# SoftPoweroff.net
KiCad netlist of a schematic drawn in EAGLE
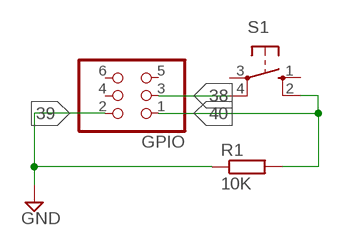
[diagram p0: schematic, sheet 1]

(export (version "E")
  (design (tool "Eeschema 10.0.6"))
  (components
    (comp (ref "GPIO")
      (value "PINHD-2X3")
      (footprint "eagle-import:2X03")
      (libsource (lib "eagle-import") (part "PINHD-2X3"))
    )
    (comp (ref "R1")
      (value "10K")
      (footprint "eagle-import:0207_10")
      (libsource (lib "eagle-import") (part "R-EU_0207/10"))
    )
    (comp (ref "S1")
      (value "10-XX")
      (footprint "eagle-import:B3F-10XX")
      (fields (field (name "MPN") "B3F-1000"))
      (libsource (lib "eagle-import") (part "10-XX"))
    )
  )
  (nets
    (net (code "1") (name "38") (class "Default")
      (node (ref "GPIO") (pin "3") (pinfunction "3_3") (pintype "passive"))
      (node (ref "S1") (pin "4") (pinfunction "P1_4") (pintype "passive"))
    )
    (net (code "2") (name "39") (class "Default")
      (node (ref "GPIO") (pin "2") (pinfunction "2_2") (pintype "passive"))
      (node (ref "R1") (pin "1") (pinfunction "1_1") (pintype "passive"))
    )
    (net (code "3") (name "40") (class "Default")
      (node (ref "GPIO") (pin "1") (pinfunction "1_1") (pintype "passive"))
      (node (ref "R1") (pin "2") (pinfunction "2_2") (pintype "passive"))
      (node (ref "S1") (pin "2") (pinfunction "S1_2") (pintype "passive"))
    )
    (net (code "4") (name "unconnected-(GPIO-Pad4)") (class "Default")
      (node (ref "GPIO") (pin "4") (pinfunction "4_4") (pintype "passive"))
    )
    (net (code "5") (name "unconnected-(GPIO-Pad5)") (class "Default")
      (node (ref "GPIO") (pin "5") (pinfunction "5_5") (pintype "passive"))
    )
    (net (code "6") (name "unconnected-(GPIO-Pad6)") (class "Default")
      (node (ref "GPIO") (pin "6") (pinfunction "6_6") (pintype "passive"))
    )
    (net (code "7") (name "unconnected-(S1-P-Pad3)") (class "Default")
      (node (ref "S1") (pin "3") (pinfunction "P_3") (pintype "passive"))
    )
    (net (code "8") (name "unconnected-(S1-S-Pad1)") (class "Default")
      (node (ref "S1") (pin "1") (pinfunction "S_1") (pintype "passive"))
    )
  )
)
